# controlled_rectifier2.net
KiCad netlist of a schematic drawn in Altium Designer
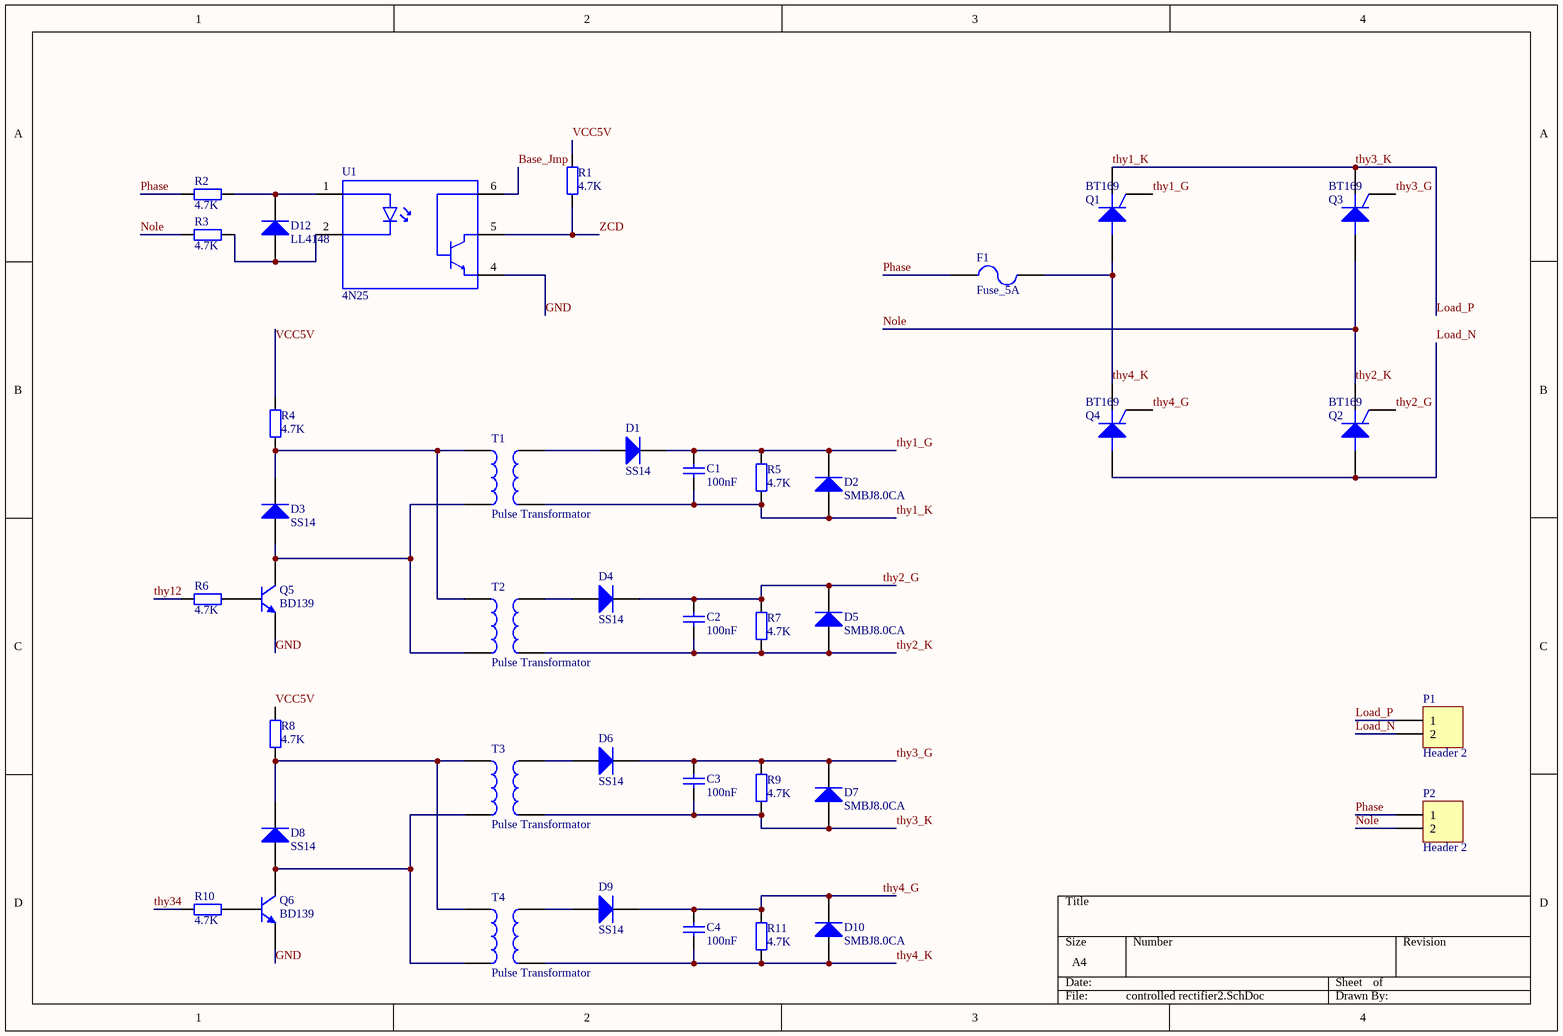
[diagram p0: controlled rectifier2.SchDoc]

(export (version "E")
  (design (tool "Eeschema 10.0.6"))
  (components
    (comp (ref "C1")
      (value "100nF")
      (footprint "CAPS_0805")
      (description "CAP 0805")
      (fields (field (name "DESIGNER") "Abbas Basereh"))
      (libsource (lib "2016AbbasBasereh9365731239-12-10-95_-275613969") (part "CAP SMD 0805"))
    )
    (comp (ref "C2")
      (value "100nF")
      (footprint "CAPS_0805")
      (description "CAP 0805")
      (fields (field (name "DESIGNER") "Abbas Basereh"))
      (libsource (lib "2016AbbasBasereh9365731239-12-10-95_-275613969") (part "CAP SMD 0805"))
    )
    (comp (ref "C3")
      (value "100nF")
      (footprint "CAPS_0805")
      (description "CAP 0805")
      (fields (field (name "DESIGNER") "Abbas Basereh"))
      (libsource (lib "2016AbbasBasereh9365731239-12-10-95_-275613969") (part "CAP SMD 0805"))
    )
    (comp (ref "C4")
      (value "100nF")
      (footprint "CAPS_0805")
      (description "CAP 0805")
      (fields (field (name "DESIGNER") "Abbas Basereh"))
      (libsource (lib "2016AbbasBasereh9365731239-12-10-95_-275613969") (part "CAP SMD 0805"))
    )
    (comp (ref "D1")
      (value "SS14")
      (footprint "DO-214AC")
      (description "Default Diode")
      (fields (field (name "PUBLISHER") "Altium Limited"))
      (libsource (lib "Miscellaneous Devices") (part "Diode"))
    )
    (comp (ref "D2")
      (value "SMBJ8.0CA")
      (footprint "SMC")
      (description "Default Diode")
      (fields (field (name "PUBLISHER") "Altium Limited"))
      (libsource (lib "Miscellaneous Devices") (part "Diode"))
    )
    (comp (ref "D3")
      (value "SS14")
      (footprint "DO-214AC")
      (description "Default Diode")
      (fields (field (name "PUBLISHER") "Altium Limited"))
      (libsource (lib "Miscellaneous Devices") (part "Diode"))
    )
    (comp (ref "D4")
      (value "SS14")
      (footprint "DO-214AC")
      (description "Default Diode")
      (fields (field (name "PUBLISHER") "Altium Limited"))
      (libsource (lib "Miscellaneous Devices") (part "Diode"))
    )
    (comp (ref "D5")
      (value "SMBJ8.0CA")
      (footprint "SMC")
      (description "Default Diode")
      (fields (field (name "PUBLISHER") "Altium Limited"))
      (libsource (lib "Miscellaneous Devices") (part "Diode"))
    )
    (comp (ref "D6")
      (value "SS14")
      (footprint "DO-214AC")
      (description "Default Diode")
      (fields (field (name "PUBLISHER") "Altium Limited"))
      (libsource (lib "Miscellaneous Devices") (part "Diode"))
    )
    (comp (ref "D7")
      (value "SMBJ8.0CA")
      (footprint "SMC")
      (description "Default Diode")
      (fields (field (name "PUBLISHER") "Altium Limited"))
      (libsource (lib "Miscellaneous Devices") (part "Diode"))
    )
    (comp (ref "D8")
      (value "SS14")
      (footprint "DO-214AC")
      (description "Default Diode")
      (fields (field (name "PUBLISHER") "Altium Limited"))
      (libsource (lib "Miscellaneous Devices") (part "Diode"))
    )
    (comp (ref "D9")
      (value "SS14")
      (footprint "DO-214AC")
      (description "Default Diode")
      (fields (field (name "PUBLISHER") "Altium Limited"))
      (libsource (lib "Miscellaneous Devices") (part "Diode"))
    )
    (comp (ref "D10")
      (value "SMBJ8.0CA")
      (footprint "SMC")
      (description "Default Diode")
      (fields (field (name "PUBLISHER") "Altium Limited"))
      (libsource (lib "Miscellaneous Devices") (part "Diode"))
    )
    (comp (ref "D12")
      (value "LL4148")
      (footprint "SOD80, LL-34")
      (description "Default Diode")
      (fields (field (name "PUBLISHER") "Altium Limited"))
      (libsource (lib "Miscellaneous Devices") (part "Diode"))
    )
    (comp (ref "F1")
      (value "Fuse_5A")
      (footprint "fuse-2")
      (description "Fuse")
      (fields (field (name "PUBLISHER") "Altium Limited"))
      (libsource (lib "Miscellaneous Devices") (part "Fuse 2"))
    )
    (comp (ref "P1")
      (value "Header 2")
      (footprint "Phoenix 2 Pin -RA")
      (description "Header, 2-Pin")
      (fields (field (name "PUBLISHER") "Altium Limited"))
      (libsource (lib "Miscellaneous Connectors") (part "Header 2"))
    )
    (comp (ref "P2")
      (value "Header 2")
      (footprint "Phoenix 2 Pin -RA")
      (description "Header, 2-Pin")
      (fields (field (name "PUBLISHER") "Altium Limited"))
      (libsource (lib "Miscellaneous Connectors") (part "Header 2"))
    )
    (comp (ref "Q1")
      (value "BT169")
      (footprint "BT169")
      (description "Silicon Controlled Rectifier")
      (fields (field (name "PUBLISHER") "Altium Limited"))
      (libsource (lib "Miscellaneous Devices") (part "SCR"))
    )
    (comp (ref "Q2")
      (value "BT169")
      (footprint "BT169")
      (description "Silicon Controlled Rectifier")
      (fields (field (name "PUBLISHER") "Altium Limited"))
      (libsource (lib "Miscellaneous Devices") (part "SCR"))
    )
    (comp (ref "Q3")
      (value "BT169")
      (footprint "BT169")
      (description "Silicon Controlled Rectifier")
      (fields (field (name "PUBLISHER") "Altium Limited"))
      (libsource (lib "Miscellaneous Devices") (part "SCR"))
    )
    (comp (ref "Q4")
      (value "BT169")
      (footprint "BT169")
      (description "Silicon Controlled Rectifier")
      (fields (field (name "PUBLISHER") "Altium Limited"))
      (libsource (lib "Miscellaneous Devices") (part "SCR"))
    )
    (comp (ref "Q5")
      (value "BD139")
      (footprint "BD139")
      (description "NPN Bipolar Transistor")
      (fields (field (name "PUBLISHER") "Altium Limited"))
      (libsource (lib "Miscellaneous Devices") (part "NPN"))
    )
    (comp (ref "Q6")
      (value "BD139")
      (footprint "BD139")
      (description "NPN Bipolar Transistor")
      (fields (field (name "PUBLISHER") "Altium Limited"))
      (libsource (lib "Miscellaneous Devices") (part "NPN"))
    )
    (comp (ref "R1")
      (value "4.7K")
      (footprint "res_0805")
      (description "Resistor")
      (fields (field (name "PUBLISHER") "Altium Limited"))
      (libsource (lib "Miscellaneous Devices") (part "Res2"))
    )
    (comp (ref "R2")
      (value "4.7K")
      (footprint "res_0805")
      (description "Resistor")
      (fields (field (name "PUBLISHER") "Altium Limited"))
      (libsource (lib "") (part "Res2_1"))
    )
    (comp (ref "R3")
      (value "4.7K")
      (footprint "res_0805")
      (description "Resistor")
      (fields (field (name "PUBLISHER") "Altium Limited"))
      (libsource (lib "") (part "Res2_1"))
    )
    (comp (ref "R4")
      (value "4.7K")
      (footprint "res_0805")
      (description "Resistor")
      (fields (field (name "PUBLISHER") "Altium Limited"))
      (libsource (lib "Miscellaneous Devices") (part "Res2"))
    )
    (comp (ref "R5")
      (value "4.7K")
      (footprint "res_0805")
      (description "Resistor")
      (fields (field (name "PUBLISHER") "Altium Limited"))
      (libsource (lib "Miscellaneous Devices") (part "Res2"))
    )
    (comp (ref "R6")
      (value "4.7K")
      (footprint "res_0805")
      (description "Resistor")
      (fields (field (name "PUBLISHER") "Altium Limited"))
      (libsource (lib "") (part "Res2_1"))
    )
    (comp (ref "R7")
      (value "4.7K")
      (footprint "res_0805")
      (description "Resistor")
      (fields (field (name "PUBLISHER") "Altium Limited"))
      (libsource (lib "Miscellaneous Devices") (part "Res2"))
    )
    (comp (ref "R8")
      (value "4.7K")
      (footprint "res_0805")
      (description "Resistor")
      (fields (field (name "PUBLISHER") "Altium Limited"))
      (libsource (lib "Miscellaneous Devices") (part "Res2"))
    )
    (comp (ref "R9")
      (value "4.7K")
      (footprint "res_0805")
      (description "Resistor")
      (fields (field (name "PUBLISHER") "Altium Limited"))
      (libsource (lib "Miscellaneous Devices") (part "Res2"))
    )
    (comp (ref "R10")
      (value "4.7K")
      (footprint "res_0805")
      (description "Resistor")
      (fields (field (name "PUBLISHER") "Altium Limited"))
      (libsource (lib "") (part "Res2_1"))
    )
    (comp (ref "R11")
      (value "4.7K")
      (footprint "res_0805")
      (description "Resistor")
      (fields (field (name "PUBLISHER") "Altium Limited"))
      (libsource (lib "Miscellaneous Devices") (part "Res2"))
    )
    (comp (ref "T1")
      (value "Pulse Transformator")
      (footprint "Pulse Trans_Small")
      (description "Transformer")
      (fields (field (name "PUBLISHER") "Altium Limited"))
      (libsource (lib "Miscellaneous Devices") (part "Trans"))
    )
    (comp (ref "T2")
      (value "Pulse Transformator")
      (footprint "Pulse Trans_Small")
      (description "Transformer")
      (fields (field (name "PUBLISHER") "Altium Limited"))
      (libsource (lib "Miscellaneous Devices") (part "Trans"))
    )
    (comp (ref "T3")
      (value "Pulse Transformator")
      (footprint "Pulse Trans_Small")
      (description "Transformer")
      (fields (field (name "PUBLISHER") "Altium Limited"))
      (libsource (lib "Miscellaneous Devices") (part "Trans"))
    )
    (comp (ref "T4")
      (value "Pulse Transformator")
      (footprint "Pulse Trans_Small")
      (description "Transformer")
      (fields (field (name "PUBLISHER") "Altium Limited"))
      (libsource (lib "Miscellaneous Devices") (part "Trans"))
    )
    (comp (ref "U1")
      (value "4N25")
      (footprint "DIP762W50P254L712H400Q6N")
      (description "Optoisolator Transistor with Base Output 5000Vrms 1 Channel 6-DIP")
      (fields (field (name "MF") "Vishay Semiconductor"))
      (libsource (lib "altium-import") (part "root_0_4N25_"))
    )
  )
  (nets
    (net (code "1") (name "/Base_Jmp") (class "Default")
      (node (ref "U1") (pin "6") (pinfunction "B_6") (pintype "passive"))
    )
    (net (code "2") (name "/GND") (class "Default")
      (node (ref "Q5") (pin "3") (pinfunction "E_3") (pintype "passive"))
      (node (ref "Q6") (pin "3") (pinfunction "E_3") (pintype "passive"))
      (node (ref "U1") (pin "4") (pinfunction "E_4") (pintype "passive"))
    )
    (net (code "3") (name "/Load_N") (class "Default")
      (node (ref "P1") (pin "2") (pinfunction "2_2") (pintype "passive"))
      (node (ref "Q2") (pin "1") (pinfunction "A_1") (pintype "passive"))
      (node (ref "Q4") (pin "1") (pinfunction "A_1") (pintype "passive"))
    )
    (net (code "4") (name "/Load_P") (class "Default")
      (node (ref "C1") (pin "1") (pinfunction "1_1") (pintype "passive"))
      (node (ref "C3") (pin "1") (pinfunction "1_1") (pintype "passive"))
      (node (ref "D2") (pin "1") (pinfunction "A_1") (pintype "passive"))
      (node (ref "D7") (pin "1") (pinfunction "A_1") (pintype "passive"))
      (node (ref "P1") (pin "1") (pinfunction "1_1") (pintype "passive"))
      (node (ref "Q1") (pin "3") (pinfunction "K_3") (pintype "passive"))
      (node (ref "Q3") (pin "3") (pinfunction "K_3") (pintype "passive"))
      (node (ref "R5") (pin "1") (pinfunction "1_1") (pintype "passive"))
      (node (ref "R9") (pin "1") (pinfunction "1_1") (pintype "passive"))
      (node (ref "T1") (pin "4") (pinfunction "4_4") (pintype "passive"))
      (node (ref "T3") (pin "4") (pinfunction "4_4") (pintype "passive"))
    )
    (net (code "5") (name "/Nole") (class "Default")
      (node (ref "C2") (pin "1") (pinfunction "1_1") (pintype "passive"))
      (node (ref "D5") (pin "1") (pinfunction "A_1") (pintype "passive"))
      (node (ref "P2") (pin "2") (pinfunction "2_2") (pintype "passive"))
      (node (ref "Q2") (pin "3") (pinfunction "K_3") (pintype "passive"))
      (node (ref "Q3") (pin "1") (pinfunction "A_1") (pintype "passive"))
      (node (ref "R3") (pin "1") (pinfunction "1_1") (pintype "passive"))
      (node (ref "R7") (pin "1") (pinfunction "1_1") (pintype "passive"))
      (node (ref "T2") (pin "4") (pinfunction "4_4") (pintype "passive"))
    )
    (net (code "6") (name "/Phase") (class "Default")
      (node (ref "F1") (pin "1") (pinfunction "1_1") (pintype "passive"))
      (node (ref "P2") (pin "1") (pinfunction "1_1") (pintype "passive"))
      (node (ref "R2") (pin "1") (pinfunction "1_1") (pintype "passive"))
    )
    (net (code "7") (name "/VCC5V") (class "Default")
      (node (ref "R1") (pin "2") (pinfunction "2_2") (pintype "passive"))
      (node (ref "R4") (pin "2") (pinfunction "2_2") (pintype "passive"))
      (node (ref "R8") (pin "2") (pinfunction "2_2") (pintype "passive"))
    )
    (net (code "8") (name "/ZCD") (class "Default")
      (node (ref "R1") (pin "1") (pinfunction "1_1") (pintype "passive"))
      (node (ref "U1") (pin "5") (pinfunction "C_5") (pintype "passive"))
    )
    (net (code "9") (name "/thy1_G") (class "Default")
      (node (ref "C1") (pin "2") (pinfunction "2_2") (pintype "passive"))
      (node (ref "D1") (pin "2") (pinfunction "K_2") (pintype "passive"))
      (node (ref "D2") (pin "2") (pinfunction "K_2") (pintype "passive"))
      (node (ref "Q1") (pin "2") (pinfunction "G_2") (pintype "passive"))
      (node (ref "R5") (pin "2") (pinfunction "2_2") (pintype "passive"))
    )
    (net (code "10") (name "/thy2_G") (class "Default")
      (node (ref "C2") (pin "2") (pinfunction "2_2") (pintype "passive"))
      (node (ref "D4") (pin "2") (pinfunction "K_2") (pintype "passive"))
      (node (ref "D5") (pin "2") (pinfunction "K_2") (pintype "passive"))
      (node (ref "Q2") (pin "2") (pinfunction "G_2") (pintype "passive"))
      (node (ref "R7") (pin "2") (pinfunction "2_2") (pintype "passive"))
    )
    (net (code "11") (name "/thy3_G") (class "Default")
      (node (ref "C3") (pin "2") (pinfunction "2_2") (pintype "passive"))
      (node (ref "D6") (pin "2") (pinfunction "K_2") (pintype "passive"))
      (node (ref "D7") (pin "2") (pinfunction "K_2") (pintype "passive"))
      (node (ref "Q3") (pin "2") (pinfunction "G_2") (pintype "passive"))
      (node (ref "R9") (pin "2") (pinfunction "2_2") (pintype "passive"))
    )
    (net (code "12") (name "/thy4_G") (class "Default")
      (node (ref "C4") (pin "2") (pinfunction "2_2") (pintype "passive"))
      (node (ref "D10") (pin "2") (pinfunction "K_2") (pintype "passive"))
      (node (ref "D9") (pin "2") (pinfunction "K_2") (pintype "passive"))
      (node (ref "Q4") (pin "2") (pinfunction "G_2") (pintype "passive"))
      (node (ref "R11") (pin "2") (pinfunction "2_2") (pintype "passive"))
    )
    (net (code "13") (name "/thy4_K") (class "Default")
      (node (ref "C4") (pin "1") (pinfunction "1_1") (pintype "passive"))
      (node (ref "D10") (pin "1") (pinfunction "A_1") (pintype "passive"))
      (node (ref "F1") (pin "2") (pinfunction "2_2") (pintype "passive"))
      (node (ref "Q1") (pin "1") (pinfunction "A_1") (pintype "passive"))
      (node (ref "Q4") (pin "3") (pinfunction "K_3") (pintype "passive"))
      (node (ref "R11") (pin "1") (pinfunction "1_1") (pintype "passive"))
      (node (ref "T4") (pin "4") (pinfunction "4_4") (pintype "passive"))
    )
    (net (code "14") (name "/thy12") (class "Default")
      (node (ref "R6") (pin "1") (pinfunction "1_1") (pintype "passive"))
    )
    (net (code "15") (name "/thy34") (class "Default")
      (node (ref "R10") (pin "1") (pinfunction "1_1") (pintype "passive"))
    )
    (net (code "16") (name "Net-(D1-A)") (class "Default")
      (node (ref "D1") (pin "1") (pinfunction "A_1") (pintype "passive"))
      (node (ref "T1") (pin "3") (pinfunction "3_3") (pintype "passive"))
    )
    (net (code "17") (name "Net-(D3-A)") (class "Default")
      (node (ref "D3") (pin "1") (pinfunction "A_1") (pintype "passive"))
      (node (ref "Q5") (pin "1") (pinfunction "C_1") (pintype "passive"))
      (node (ref "T1") (pin "2") (pinfunction "2_2") (pintype "passive"))
      (node (ref "T2") (pin "2") (pinfunction "2_2") (pintype "passive"))
    )
    (net (code "18") (name "Net-(D3-K)") (class "Default")
      (node (ref "D3") (pin "2") (pinfunction "K_2") (pintype "passive"))
      (node (ref "R4") (pin "1") (pinfunction "1_1") (pintype "passive"))
      (node (ref "T1") (pin "1") (pinfunction "1_1") (pintype "passive"))
      (node (ref "T2") (pin "1") (pinfunction "1_1") (pintype "passive"))
    )
    (net (code "19") (name "Net-(D4-A)") (class "Default")
      (node (ref "D4") (pin "1") (pinfunction "A_1") (pintype "passive"))
      (node (ref "T2") (pin "3") (pinfunction "3_3") (pintype "passive"))
    )
    (net (code "20") (name "Net-(D6-A)") (class "Default")
      (node (ref "D6") (pin "1") (pinfunction "A_1") (pintype "passive"))
      (node (ref "T3") (pin "3") (pinfunction "3_3") (pintype "passive"))
    )
    (net (code "21") (name "Net-(D8-A)") (class "Default")
      (node (ref "D8") (pin "1") (pinfunction "A_1") (pintype "passive"))
      (node (ref "Q6") (pin "1") (pinfunction "C_1") (pintype "passive"))
      (node (ref "T3") (pin "2") (pinfunction "2_2") (pintype "passive"))
      (node (ref "T4") (pin "2") (pinfunction "2_2") (pintype "passive"))
    )
    (net (code "22") (name "Net-(D8-K)") (class "Default")
      (node (ref "D8") (pin "2") (pinfunction "K_2") (pintype "passive"))
      (node (ref "R8") (pin "1") (pinfunction "1_1") (pintype "passive"))
      (node (ref "T3") (pin "1") (pinfunction "1_1") (pintype "passive"))
      (node (ref "T4") (pin "1") (pinfunction "1_1") (pintype "passive"))
    )
    (net (code "23") (name "Net-(D9-A)") (class "Default")
      (node (ref "D9") (pin "1") (pinfunction "A_1") (pintype "passive"))
      (node (ref "T4") (pin "3") (pinfunction "3_3") (pintype "passive"))
    )
    (net (code "24") (name "Net-(D12-A)") (class "Default")
      (node (ref "D12") (pin "1") (pinfunction "A_1") (pintype "passive"))
      (node (ref "R3") (pin "2") (pinfunction "2_2") (pintype "passive"))
      (node (ref "U1") (pin "2") (pinfunction "K_2") (pintype "passive"))
    )
    (net (code "25") (name "Net-(D12-K)") (class "Default")
      (node (ref "D12") (pin "2") (pinfunction "K_2") (pintype "passive"))
      (node (ref "R2") (pin "2") (pinfunction "2_2") (pintype "passive"))
      (node (ref "U1") (pin "1") (pinfunction "A_1") (pintype "passive"))
    )
    (net (code "26") (name "Net-(Q5-B)") (class "Default")
      (node (ref "Q5") (pin "2") (pinfunction "B_2") (pintype "passive"))
      (node (ref "R6") (pin "2") (pinfunction "2_2") (pintype "passive"))
    )
    (net (code "27") (name "Net-(Q6-B)") (class "Default")
      (node (ref "Q6") (pin "2") (pinfunction "B_2") (pintype "passive"))
      (node (ref "R10") (pin "2") (pinfunction "2_2") (pintype "passive"))
    )
  )
)
